# ProPrj_X-Link_OB-RA4M2_M_2024-12-16.net
KiCad netlist of a schematic drawn in EasyEDA Pro
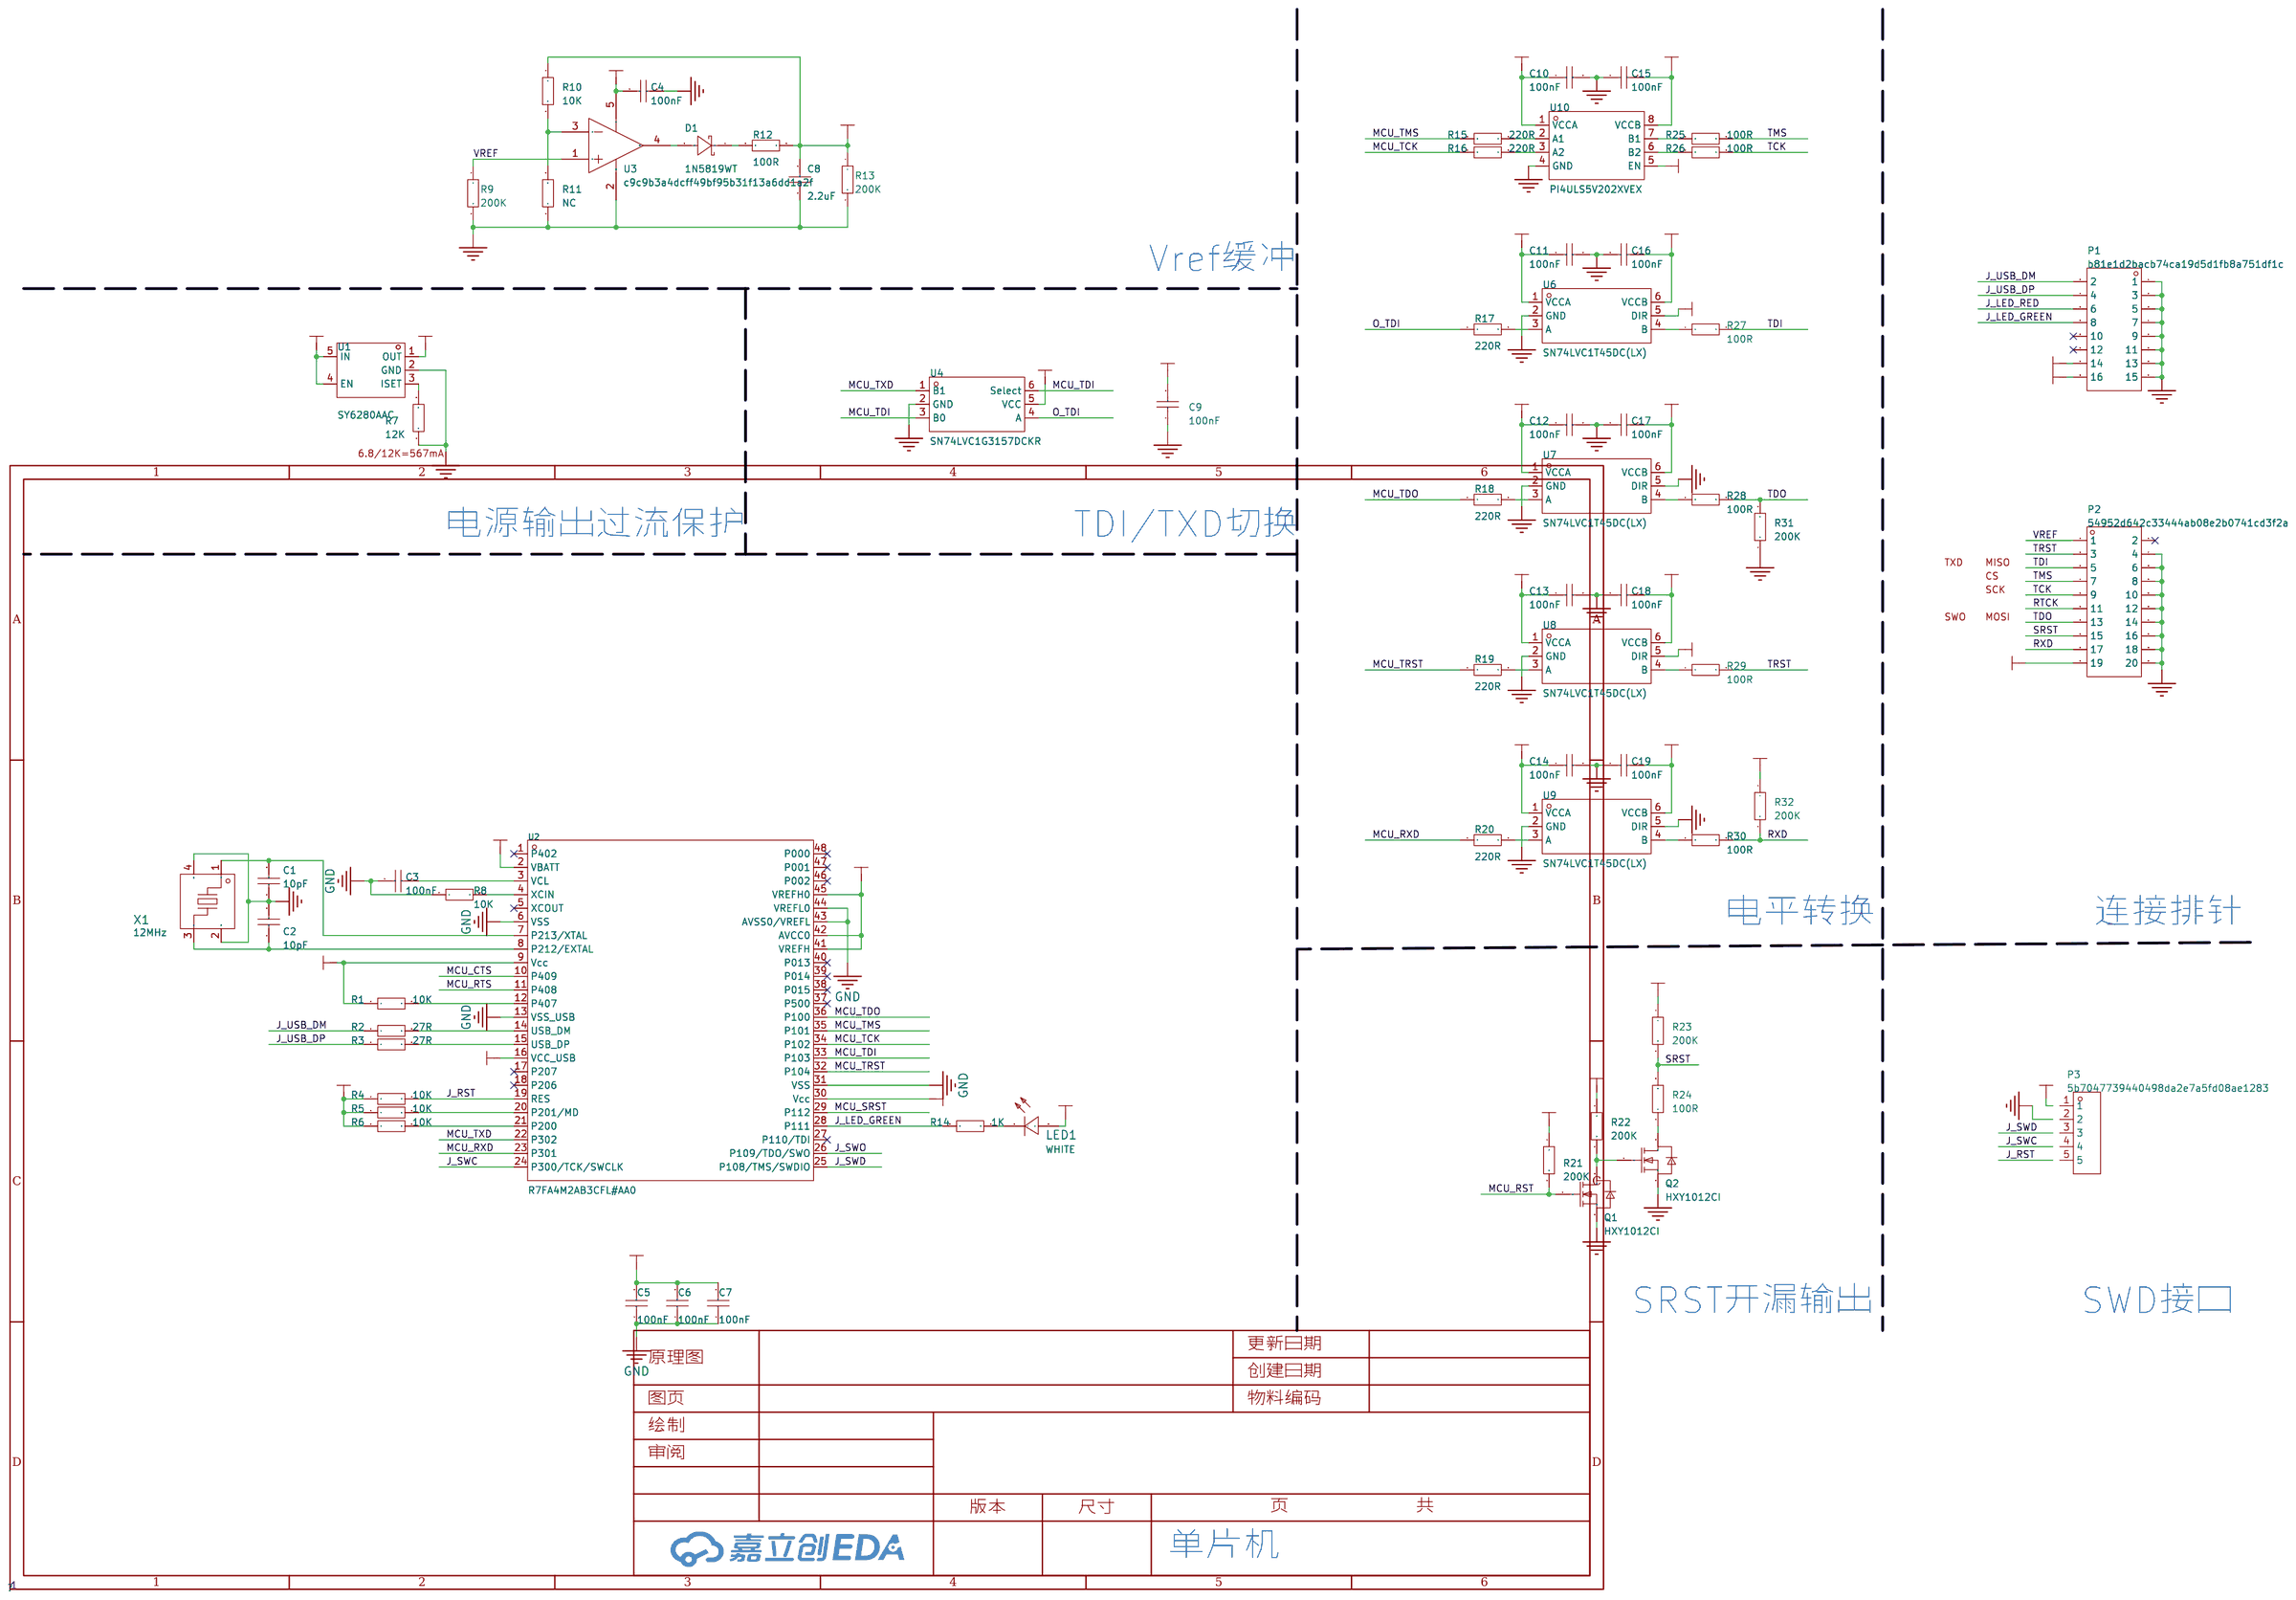
[diagram p0: schematic sheet]

(export (version "E")
  (design (tool "Eeschema 10.0.6"))
  (components
    (comp (ref "C1")
      (value "10pF")
      (footprint "easyedapro:C0805")
      (description "容值:20pF;精度:±5%;额定电压:50V;材质(温度系数):C0G;")
      (fields
        (field (name "Manufacturer Part") "CL21C200JBANNNC")
        (field (name "Manufacturer") "SAMSUNG(三星)")
      )
      (libsource (lib "easyedapro") (part "CL21C200JBANNNC"))
    )
    (comp (ref "C2")
      (value "10pF")
      (footprint "easyedapro:C0805")
      (description "容值:20pF;精度:±5%;额定电压:50V;材质(温度系数):C0G;")
      (fields
        (field (name "Manufacturer Part") "CL21C200JBANNNC")
        (field (name "Manufacturer") "SAMSUNG(三星)")
      )
      (libsource (lib "easyedapro") (part "CL21C200JBANNNC"))
    )
    (comp (ref "C3")
      (value "100nF")
      (footprint "easyedapro:C0805")
      (description "容值:100nF;精度:±10%;额定电压:50V;材质(温度系数):X7R;")
      (fields
        (field (name "Manufacturer Part") "CC0805KRX7R9BB104")
        (field (name "Manufacturer") "YAGEO(国巨)")
      )
      (libsource (lib "easyedapro") (part "CC0805KRX7R9BB104"))
    )
    (comp (ref "C4")
      (value "100nF")
      (footprint "easyedapro:C0402")
      (libsource (lib "easyedapro") (part "C0402"))
    )
    (comp (ref "C5")
      (value "100nF")
      (footprint "easyedapro:C0805")
      (description "容值:100nF;精度:±10%;额定电压:50V;材质(温度系数):X7R;")
      (fields
        (field (name "Manufacturer Part") "CC0805KRX7R9BB104")
        (field (name "Manufacturer") "YAGEO(国巨)")
      )
      (libsource (lib "easyedapro") (part "CC0805KRX7R9BB104"))
    )
    (comp (ref "C6")
      (value "100nF")
      (footprint "easyedapro:C0805")
      (description "容值:100nF;精度:±10%;额定电压:50V;材质(温度系数):X7R;")
      (fields
        (field (name "Manufacturer Part") "CC0805KRX7R9BB104")
        (field (name "Manufacturer") "YAGEO(国巨)")
      )
      (libsource (lib "easyedapro") (part "CC0805KRX7R9BB104"))
    )
    (comp (ref "C7")
      (value "100nF")
      (footprint "easyedapro:C0805")
      (description "容值:100nF;精度:±10%;额定电压:50V;材质(温度系数):X7R;")
      (fields
        (field (name "Manufacturer Part") "CC0805KRX7R9BB104")
        (field (name "Manufacturer") "YAGEO(国巨)")
      )
      (libsource (lib "easyedapro") (part "CC0805KRX7R9BB104"))
    )
    (comp (ref "C8")
      (value "2.2uF")
      (footprint "easyedapro:C0402")
      (libsource (lib "easyedapro") (part "C0402"))
    )
    (comp (ref "C9")
      (value "100nF")
      (footprint "easyedapro:C0603")
      (libsource (lib "easyedapro") (part "C0603"))
    )
    (comp (ref "C10")
      (value "100nF")
      (footprint "easyedapro:C0603")
      (libsource (lib "easyedapro") (part "C0603"))
    )
    (comp (ref "C11")
      (value "100nF")
      (footprint "easyedapro:C0603")
      (libsource (lib "easyedapro") (part "C0603"))
    )
    (comp (ref "C12")
      (value "100nF")
      (footprint "easyedapro:C0603")
      (libsource (lib "easyedapro") (part "C0603"))
    )
    (comp (ref "C13")
      (value "100nF")
      (footprint "easyedapro:C0603")
      (libsource (lib "easyedapro") (part "C0603"))
    )
    (comp (ref "C14")
      (value "100nF")
      (footprint "easyedapro:C0603")
      (libsource (lib "easyedapro") (part "C0603"))
    )
    (comp (ref "C15")
      (value "100nF")
      (footprint "easyedapro:C0603")
      (libsource (lib "easyedapro") (part "C0603"))
    )
    (comp (ref "C16")
      (value "100nF")
      (footprint "easyedapro:C0603")
      (libsource (lib "easyedapro") (part "C0603"))
    )
    (comp (ref "C17")
      (value "100nF")
      (footprint "easyedapro:C0603")
      (libsource (lib "easyedapro") (part "C0603"))
    )
    (comp (ref "C18")
      (value "100nF")
      (footprint "easyedapro:C0603")
      (libsource (lib "easyedapro") (part "C0603"))
    )
    (comp (ref "C19")
      (value "100nF")
      (footprint "easyedapro:C0603")
      (libsource (lib "easyedapro") (part "C0603"))
    )
    (comp (ref "D1")
      (value "1N5819WT")
      (footprint "easyedapro:SOD-523_L1.2-W0.8-LS1.6-RD")
      (description "二极管配置:独立式;正向压降(Vf):600mV@200mA;直流反向耐压(Vr):40V;整流电流:350mA;")
      (fields (field (name "Manufacturer") "Slkor(萨科微)"))
      (libsource (lib "easyedapro") (part "1N5819WT_C5185918"))
    )
    (comp (ref "LED1")
      (value "WHITE")
      (footprint "easyedapro:LED0603")
      (libsource (lib "easyedapro") (part "LED0603"))
    )
    (comp (ref "P1")
      (value "b81e1d2bacb74ca19d5d1fb8a751df1c")
      (footprint "easyedapro:HDR-TH_16P-P1.27-V-M-R2-C8-S1.27-1")
      (libsource (lib "easyedapro") (part "HDR2x8_1.27"))
    )
    (comp (ref "P2")
      (value "54952d642c33444ab08e2b0741cd3f2a")
      (footprint "easyedapro:HDR-TH_20P-P1.27-V-M-R2-C10-S1.27")
      (libsource (lib "easyedapro") (part "HDR2x10_1.27"))
    )
    (comp (ref "P3")
      (value "5b7047739440498da2e7a5fd08ae1283")
      (footprint "easyedapro:HDR-TH_5P-P1.27-V-M")
      (libsource (lib "easyedapro") (part "HDR1x5_1.27"))
    )
    (comp (ref "Q1")
      (value "HXY1012CI")
      (footprint "easyedapro:SOT-523-3_L1.6-W0.8-P0.50-LS1.6-BR")
      (fields (field (name "Manufacturer") "HXY MOSFET(华轩阳电子)"))
      (libsource (lib "easyedapro") (part "HXY1012CI"))
    )
    (comp (ref "Q2")
      (value "HXY1012CI")
      (footprint "easyedapro:SOT-523-3_L1.6-W0.8-P0.50-LS1.6-BR")
      (fields (field (name "Manufacturer") "HXY MOSFET(华轩阳电子)"))
      (libsource (lib "easyedapro") (part "HXY1012CI"))
    )
    (comp (ref "R1")
      (value "10K")
      (footprint "easyedapro:R0805")
      (description "阻值:10kΩ;精度:±1%;功率:125mW;温度系数:±100ppm/°C;最大工作电压:150V;工作温度范围:-55°C~+155°C;")
      (fields (field (name "Manufacturer Part") "RC0805FR-0710KL") (field (name "Manufacturer") "YAGEO(国巨)"))
      (libsource (lib "easyedapro") (part "RC0805FR-0710KL"))
    )
    (comp (ref "R2")
      (value "27R")
      (footprint "easyedapro:R0805")
      (description "电阻类型:厚膜电阻;阻值:27Ω;精度:±1%;功率:125mW;")
      (fields (field (name "Manufacturer Part") "RC0805FR-0727RL") (field (name "Manufacturer") "YAGEO(国巨)"))
      (libsource (lib "easyedapro") (part "RC0805FR-0727RL"))
    )
    (comp (ref "R3")
      (value "27R")
      (footprint "easyedapro:R0805")
      (description "电阻类型:厚膜电阻;阻值:27Ω;精度:±1%;功率:125mW;")
      (fields (field (name "Manufacturer Part") "RC0805FR-0727RL") (field (name "Manufacturer") "YAGEO(国巨)"))
      (libsource (lib "easyedapro") (part "RC0805FR-0727RL"))
    )
    (comp (ref "R4")
      (value "10K")
      (footprint "easyedapro:R0805")
      (description "阻值:10kΩ;精度:±1%;功率:125mW;温度系数:±100ppm/°C;最大工作电压:150V;工作温度范围:-55°C~+155°C;")
      (fields (field (name "Manufacturer Part") "RC0805FR-0710KL") (field (name "Manufacturer") "YAGEO(国巨)"))
      (libsource (lib "easyedapro") (part "RC0805FR-0710KL"))
    )
    (comp (ref "R5")
      (value "10K")
      (footprint "easyedapro:R0805")
      (description "阻值:10kΩ;精度:±1%;功率:125mW;温度系数:±100ppm/°C;最大工作电压:150V;工作温度范围:-55°C~+155°C;")
      (fields (field (name "Manufacturer Part") "RC0805FR-0710KL") (field (name "Manufacturer") "YAGEO(国巨)"))
      (libsource (lib "easyedapro") (part "RC0805FR-0710KL"))
    )
    (comp (ref "R6")
      (value "10K")
      (footprint "easyedapro:R0805")
      (description "阻值:10kΩ;精度:±1%;功率:125mW;温度系数:±100ppm/°C;最大工作电压:150V;工作温度范围:-55°C~+155°C;")
      (fields (field (name "Manufacturer Part") "RC0805FR-0710KL") (field (name "Manufacturer") "YAGEO(国巨)"))
      (libsource (lib "easyedapro") (part "RC0805FR-0710KL"))
    )
    (comp (ref "R7")
      (value "12K")
      (footprint "easyedapro:R0603")
      (libsource (lib "easyedapro") (part "R0603"))
    )
    (comp (ref "R8")
      (value "10K")
      (footprint "easyedapro:R0805")
      (description "阻值:10kΩ;精度:±1%;功率:125mW;温度系数:±100ppm/°C;最大工作电压:150V;工作温度范围:-55°C~+155°C;")
      (fields (field (name "Manufacturer Part") "RC0805FR-0710KL") (field (name "Manufacturer") "YAGEO(国巨)"))
      (libsource (lib "easyedapro") (part "RC0805FR-0710KL"))
    )
    (comp (ref "R9")
      (value "200K")
      (footprint "easyedapro:R0402")
      (libsource (lib "easyedapro") (part "R0402"))
    )
    (comp (ref "R10")
      (value "10K")
      (footprint "easyedapro:R0402")
      (libsource (lib "easyedapro") (part "R0402"))
    )
    (comp (ref "R11")
      (value "NC")
      (footprint "easyedapro:R0402")
      (libsource (lib "easyedapro") (part "R0402"))
    )
    (comp (ref "R12")
      (value "100R")
      (footprint "easyedapro:R0402")
      (libsource (lib "easyedapro") (part "R0402"))
    )
    (comp (ref "R13")
      (value "200K")
      (footprint "easyedapro:R0402")
      (libsource (lib "easyedapro") (part "R0402"))
    )
    (comp (ref "R14")
      (value "1K")
      (footprint "easyedapro:R0805")
      (description "电阻类型:厚膜电阻;阻值:5.1kΩ;精度:±1%;功率:125mW;")
      (fields
        (field (name "Manufacturer Part") "0805W8F5101T5E")
        (field (name "Manufacturer") "UNI-ROYAL(厚声)")
      )
      (libsource (lib "easyedapro") (part "0805W8F5101T5E"))
    )
    (comp (ref "R15") (value "220R") (libsource (lib "easyedapro") (part "电阻")))
    (comp (ref "R16") (value "220R") (libsource (lib "easyedapro") (part "电阻")))
    (comp (ref "R17")
      (value "220R")
      (footprint "easyedapro:R0603")
      (libsource (lib "easyedapro") (part "R0603"))
    )
    (comp (ref "R18")
      (value "220R")
      (footprint "easyedapro:R0603")
      (libsource (lib "easyedapro") (part "R0603"))
    )
    (comp (ref "R19")
      (value "220R")
      (footprint "easyedapro:R0603")
      (libsource (lib "easyedapro") (part "R0603"))
    )
    (comp (ref "R20")
      (value "220R")
      (footprint "easyedapro:R0603")
      (libsource (lib "easyedapro") (part "R0603"))
    )
    (comp (ref "R21") (value "200K") (libsource (lib "easyedapro") (part "电阻")))
    (comp (ref "R22") (value "200K") (libsource (lib "easyedapro") (part "电阻")))
    (comp (ref "R23") (value "200K") (libsource (lib "easyedapro") (part "电阻")))
    (comp (ref "R24") (value "100R") (libsource (lib "easyedapro") (part "电阻")))
    (comp (ref "R25") (value "100R") (libsource (lib "easyedapro") (part "电阻")))
    (comp (ref "R26") (value "100R") (libsource (lib "easyedapro") (part "电阻")))
    (comp (ref "R27")
      (value "100R")
      (footprint "easyedapro:R0603")
      (libsource (lib "easyedapro") (part "R0603"))
    )
    (comp (ref "R28")
      (value "100R")
      (footprint "easyedapro:R0603")
      (libsource (lib "easyedapro") (part "R0603"))
    )
    (comp (ref "R29")
      (value "100R")
      (footprint "easyedapro:R0603")
      (libsource (lib "easyedapro") (part "R0603"))
    )
    (comp (ref "R30")
      (value "100R")
      (footprint "easyedapro:R0603")
      (libsource (lib "easyedapro") (part "R0603"))
    )
    (comp (ref "R31")
      (value "200K")
      (footprint "easyedapro:R0603")
      (libsource (lib "easyedapro") (part "R0603"))
    )
    (comp (ref "R32")
      (value "200K")
      (footprint "easyedapro:R0603")
      (libsource (lib "easyedapro") (part "R0603"))
    )
    (comp (ref "U1")
      (value "SY6280AAC")
      (footprint "easyedapro:SOT-23-5_L3.0-W1.7-P0.95-LS2.8-BL")
      (description "低能耗配电开关")
      (fields (field (name "Manufacturer") "silergy(矽力杰)"))
      (libsource (lib "easyedapro") (part "SY6280AAC"))
    )
    (comp (ref "U2")
      (value "R7FA4M2AB3CFL#AA0")
      (footprint "easyedapro:LQFP-48_L7.0-W7.0-P0.50-LS9.0-BL")
      (description "CPU内核:ARM-M系列;CPU最大主频:100MHz;工作电压范围:2.7V~3.6V;程序存储容量:254KB;GPIO端口数量:30;")
      (fields (field (name "Manufacturer") "RENESAS(瑞萨)/IDT"))
      (libsource (lib "easyedapro") (part "R7FA4M2AB3CFL#AA0"))
    )
    (comp (ref "U3")
      (value "c9c9b3a4dcff49bf95b31f13a6dd1a2f")
      (footprint "easyedapro:SOT-23-5_L2.9-W1.6-P0.95-LS2.8-BR")
      (description "轨到轨输入输出单运放")
      (fields (field (name "Manufacturer Part") "LMV321"))
      (libsource (lib "easyedapro") (part "LMV321"))
    )
    (comp (ref "U4")
      (value "SN74LVC1G3157DCKR")
      (footprint "easyedapro:SC70-6_L2.1-W1.3-P0.65-LS2.3-BL")
      (description "开关电路:单刀双掷(SPDT)-常开/常闭;通道数:1;导通电阻(Ron@VCC):7Ω;")
      (fields (field (name "Manufacturer") "UMW(友台半导体)"))
      (libsource (lib "easyedapro") (part "SN74LVC1G3157DCKR-1"))
    )
    (comp (ref "U6")
      (value "SN74LVC1T45DC(LX)")
      (footprint "easyedapro:SC-70-6_L2.2-W1.3-P0.65-LS2.1-BR")
      (description "电压(VCCA):1.65V~5.5V;电压(VCCB):1.65V~5.5V;电路数:1;每个电路通道数:1;")
      (fields (field (name "Manufacturer") "LX(灵星芯微)"))
      (libsource (lib "easyedapro") (part "74LVC1T45DW-7"))
    )
    (comp (ref "U7")
      (value "SN74LVC1T45DC(LX)")
      (footprint "easyedapro:SC-70-6_L2.2-W1.3-P0.65-LS2.1-BR")
      (description "电压(VCCA):1.65V~5.5V;电压(VCCB):1.65V~5.5V;电路数:1;每个电路通道数:1;")
      (fields (field (name "Manufacturer") "LX(灵星芯微)"))
      (libsource (lib "easyedapro") (part "74LVC1T45DW-7"))
    )
    (comp (ref "U8")
      (value "SN74LVC1T45DC(LX)")
      (footprint "easyedapro:SC-70-6_L2.2-W1.3-P0.65-LS2.1-BR")
      (description "电压(VCCA):1.65V~5.5V;电压(VCCB):1.65V~5.5V;电路数:1;每个电路通道数:1;")
      (fields (field (name "Manufacturer") "LX(灵星芯微)"))
      (libsource (lib "easyedapro") (part "74LVC1T45DW-7"))
    )
    (comp (ref "U9")
      (value "SN74LVC1T45DC(LX)")
      (footprint "easyedapro:SC-70-6_L2.2-W1.3-P0.65-LS2.1-BR")
      (description "电压(VCCA):1.65V~5.5V;电压(VCCB):1.65V~5.5V;电路数:1;每个电路通道数:1;")
      (fields (field (name "Manufacturer") "LX(灵星芯微)"))
      (libsource (lib "easyedapro") (part "74LVC1T45DW-7"))
    )
    (comp (ref "U10")
      (value "PI4ULS5V202XVEX")
      (footprint "easyedapro:UDFN-8_L1.6-W1.2-P0.40-BL")
      (description "数据速率:20Mbps;电压(VCCA):1.2V~5.5V;电压(VCCB):1.2V~5.5V;电路数:1;每个电路通道数:2;")
      (fields (field (name "Manufacturer") "DIODES(美台)"))
      (libsource (lib "easyedapro") (part "PI4ULS5V202XVEX"))
    )
    (comp (ref "X1")
      (value "12MHz")
      (footprint "easyedapro:CRYSTAL-SMD_4P-L3.2-W2.5-BL-A")
      (libsource (lib "easyedapro") (part "XTAL3225"))
    )
  )
  (nets
    (net (code "1") (name "/J_LED_GREEN") (class "Default")
      (node (ref "P1") (pin "8") (pinfunction "8_8") (pintype "unspecified"))
      (node (ref "R14") (pin "1") (pinfunction "1_1") (pintype "input"))
      (node (ref "U2") (pin "28") (pinfunction "P111_28") (pintype "input"))
    )
    (net (code "2") (name "/J_LED_RED") (class "Default")
      (node (ref "P1") (pin "6") (pinfunction "6_6") (pintype "unspecified"))
    )
    (net (code "3") (name "/J_RST") (class "Default")
      (node (ref "R4") (pin "2") (pinfunction "2_2") (pintype "input"))
      (node (ref "U2") (pin "19") (pinfunction "RES_19") (pintype "input"))
    )
    (net (code "4") (name "/J_SWC") (class "Default")
      (node (ref "U2") (pin "24") (pinfunction "P300/TCK/SWCLK_24") (pintype "input"))
    )
    (net (code "5") (name "/J_SWD") (class "Default")
      (node (ref "U2") (pin "25") (pinfunction "P108/TMS/SWDIO_25") (pintype "input"))
    )
    (net (code "6") (name "/J_SWO") (class "Default")
      (node (ref "U2") (pin "26") (pinfunction "P109/TDO/SWO_26") (pintype "input"))
    )
    (net (code "7") (name "/J_USB_DM") (class "Default")
      (node (ref "P1") (pin "2") (pinfunction "2_2") (pintype "unspecified"))
      (node (ref "R2") (pin "1") (pinfunction "1_1") (pintype "input"))
    )
    (net (code "8") (name "/J_USB_DP") (class "Default")
      (node (ref "P1") (pin "4") (pinfunction "4_4") (pintype "unspecified"))
      (node (ref "R3") (pin "1") (pinfunction "1_1") (pintype "input"))
    )
    (net (code "9") (name "/MCU_CTS") (class "Default")
      (node (ref "U2") (pin "10") (pinfunction "P409_10") (pintype "input"))
    )
    (net (code "10") (name "/MCU_RST") (class "Default")
      (node (ref "Q1") (pin "1") (pinfunction "G_1") (pintype "unspecified"))
      (node (ref "R21") (pin "2") (pinfunction "2_2") (pintype "input"))
    )
    (net (code "11") (name "/MCU_RTS") (class "Default")
      (node (ref "U2") (pin "11") (pinfunction "P408_11") (pintype "input"))
    )
    (net (code "12") (name "/MCU_RXD") (class "Default")
      (node (ref "R20") (pin "1") (pinfunction "1_1") (pintype "input"))
      (node (ref "U2") (pin "23") (pinfunction "P301_23") (pintype "input"))
    )
    (net (code "13") (name "/MCU_SRST") (class "Default")
      (node (ref "U2") (pin "29") (pinfunction "P112_29") (pintype "input"))
    )
    (net (code "14") (name "/MCU_TCK") (class "Default")
      (node (ref "R16") (pin "1") (pinfunction "1_1") (pintype "input"))
      (node (ref "U2") (pin "34") (pinfunction "P102_34") (pintype "input"))
    )
    (net (code "15") (name "/MCU_TDI") (class "Default")
      (node (ref "U2") (pin "33") (pinfunction "P103_33") (pintype "input"))
      (node (ref "U4") (pin "3") (pinfunction "B0_3") (pintype "unspecified"))
      (node (ref "U4") (pin "6") (pinfunction "Select_6") (pintype "unspecified"))
    )
    (net (code "16") (name "/MCU_TDO") (class "Default")
      (node (ref "R18") (pin "1") (pinfunction "1_1") (pintype "input"))
      (node (ref "U2") (pin "36") (pinfunction "P100_36") (pintype "input"))
    )
    (net (code "17") (name "/MCU_TMS") (class "Default")
      (node (ref "R15") (pin "1") (pinfunction "1_1") (pintype "input"))
      (node (ref "U2") (pin "35") (pinfunction "P101_35") (pintype "input"))
    )
    (net (code "18") (name "/MCU_TRST") (class "Default")
      (node (ref "R19") (pin "1") (pinfunction "1_1") (pintype "input"))
      (node (ref "U2") (pin "32") (pinfunction "P104_32") (pintype "input"))
    )
    (net (code "19") (name "/MCU_TXD") (class "Default")
      (node (ref "U2") (pin "22") (pinfunction "P302_22") (pintype "input"))
      (node (ref "U4") (pin "1") (pinfunction "B1_1") (pintype "unspecified"))
    )
    (net (code "20") (name "/O_TDI") (class "Default")
      (node (ref "R17") (pin "1") (pinfunction "1_1") (pintype "input"))
      (node (ref "U4") (pin "4") (pinfunction "A_4") (pintype "unspecified"))
    )
    (net (code "21") (name "/RTCK") (class "Default")
      (node (ref "P2") (pin "11") (pinfunction "11_11") (pintype "unspecified"))
    )
    (net (code "22") (name "/RXD") (class "Default")
      (node (ref "P2") (pin "17") (pinfunction "17_17") (pintype "unspecified"))
      (node (ref "R30") (pin "2") (pinfunction "2_2") (pintype "input"))
      (node (ref "R32") (pin "2") (pinfunction "2_2") (pintype "input"))
    )
    (net (code "23") (name "/SRST") (class "Default")
      (node (ref "P2") (pin "15") (pinfunction "15_15") (pintype "unspecified"))
      (node (ref "R23") (pin "2") (pinfunction "2_2") (pintype "input"))
      (node (ref "R24") (pin "2") (pinfunction "2_2") (pintype "input"))
    )
    (net (code "24") (name "/TCK") (class "Default")
      (node (ref "P2") (pin "9") (pinfunction "9_9") (pintype "unspecified"))
      (node (ref "R26") (pin "2") (pinfunction "2_2") (pintype "input"))
    )
    (net (code "25") (name "/TDI") (class "Default")
      (node (ref "P2") (pin "5") (pinfunction "5_5") (pintype "unspecified"))
      (node (ref "R27") (pin "2") (pinfunction "2_2") (pintype "input"))
    )
    (net (code "26") (name "/TDO") (class "Default")
      (node (ref "P2") (pin "13") (pinfunction "13_13") (pintype "unspecified"))
      (node (ref "R28") (pin "2") (pinfunction "2_2") (pintype "input"))
      (node (ref "R31") (pin "2") (pinfunction "2_2") (pintype "input"))
    )
    (net (code "27") (name "/TMS") (class "Default")
      (node (ref "P2") (pin "7") (pinfunction "7_7") (pintype "unspecified"))
      (node (ref "R25") (pin "2") (pinfunction "2_2") (pintype "input"))
    )
    (net (code "28") (name "/TRST") (class "Default")
      (node (ref "P2") (pin "3") (pinfunction "3_3") (pintype "unspecified"))
      (node (ref "R29") (pin "2") (pinfunction "2_2") (pintype "input"))
    )
    (net (code "29") (name "/VREF") (class "Default")
      (node (ref "P2") (pin "1") (pinfunction "1_1") (pintype "unspecified"))
      (node (ref "R9") (pin "1") (pinfunction "1_1") (pintype "input"))
      (node (ref "U3") (pin "1") (pinfunction "+IN_1") (pintype "unspecified"))
    )
    (net (code "30") (name "3.3V") (class "Default")
      (node (ref "C10") (pin "1") (pinfunction "1_1") (pintype "input"))
      (node (ref "C11") (pin "1") (pinfunction "1_1") (pintype "input"))
      (node (ref "C12") (pin "1") (pinfunction "1_1") (pintype "input"))
      (node (ref "C13") (pin "1") (pinfunction "1_1") (pintype "input"))
      (node (ref "C14") (pin "1") (pinfunction "1_1") (pintype "input"))
      (node (ref "C5") (pin "2") (pinfunction "2_2") (pintype "input"))
      (node (ref "C6") (pin "2") (pinfunction "2_2") (pintype "input"))
      (node (ref "C7") (pin "2") (pinfunction "2_2") (pintype "input"))
      (node (ref "C9") (pin "2") (pinfunction "2_2") (pintype "input"))
      (node (ref "LED1") (pin "2") (pinfunction "+_2") (pintype "input"))
      (node (ref "P1") (pin "14") (pinfunction "14_14") (pintype "unspecified"))
      (node (ref "R1") (pin "1") (pinfunction "1_1") (pintype "input"))
      (node (ref "R21") (pin "1") (pinfunction "1_1") (pintype "input"))
      (node (ref "R22") (pin "1") (pinfunction "1_1") (pintype "input"))
      (node (ref "R4") (pin "1") (pinfunction "1_1") (pintype "input"))
      (node (ref "R5") (pin "1") (pinfunction "1_1") (pintype "input"))
      (node (ref "R6") (pin "1") (pinfunction "1_1") (pintype "input"))
      (node (ref "U10") (pin "1") (pinfunction "VCCA_1") (pintype "unspecified"))
      (node (ref "U10") (pin "5") (pinfunction "EN_5") (pintype "unspecified"))
      (node (ref "U2") (pin "16") (pinfunction "VCC_USB_16") (pintype "input"))
      (node (ref "U2") (pin "2") (pinfunction "VBATT_2") (pintype "input"))
      (node (ref "U2") (pin "30") (pinfunction "Vcc_30") (pintype "input"))
      (node (ref "U2") (pin "41") (pinfunction "VREFH_41") (pintype "input"))
      (node (ref "U2") (pin "42") (pinfunction "AVCC0_42") (pintype "input"))
      (node (ref "U2") (pin "45") (pinfunction "VREFH0_45") (pintype "input"))
      (node (ref "U2") (pin "9") (pinfunction "Vcc_9") (pintype "input"))
      (node (ref "U4") (pin "5") (pinfunction "VCC_5") (pintype "unspecified"))
      (node (ref "U6") (pin "1") (pinfunction "VCCA_1") (pintype "unspecified"))
      (node (ref "U6") (pin "5") (pinfunction "DIR_5") (pintype "unspecified"))
      (node (ref "U7") (pin "1") (pinfunction "VCCA_1") (pintype "unspecified"))
      (node (ref "U8") (pin "1") (pinfunction "VCCA_1") (pintype "unspecified"))
      (node (ref "U8") (pin "5") (pinfunction "DIR_5") (pintype "unspecified"))
      (node (ref "U9") (pin "1") (pinfunction "VCCA_1") (pintype "unspecified"))
    )
    (net (code "31") (name "5V") (class "Default")
      (node (ref "C4") (pin "1") (pinfunction "1_1") (pintype "input"))
      (node (ref "P1") (pin "16") (pinfunction "16_16") (pintype "unspecified"))
      (node (ref "U1") (pin "4") (pinfunction "EN_4") (pintype "unspecified"))
      (node (ref "U1") (pin "5") (pinfunction "IN_5") (pintype "unspecified"))
      (node (ref "U3") (pin "5") (pinfunction "VCC+_5") (pintype "unspecified"))
    )
    (net (code "32") (name "5V_OUT") (class "Default")
      (node (ref "P2") (pin "19") (pinfunction "19_19") (pintype "unspecified"))
      (node (ref "U1") (pin "1") (pinfunction "OUT_1") (pintype "unspecified"))
    )
    (net (code "33") (name "GND") (class "Default")
      (node (ref "C1") (pin "1") (pinfunction "1_1") (pintype "input"))
      (node (ref "C10") (pin "2") (pinfunction "2_2") (pintype "input"))
      (node (ref "C11") (pin "2") (pinfunction "2_2") (pintype "input"))
      (node (ref "C12") (pin "2") (pinfunction "2_2") (pintype "input"))
      (node (ref "C13") (pin "2") (pinfunction "2_2") (pintype "input"))
      (node (ref "C14") (pin "2") (pinfunction "2_2") (pintype "input"))
      (node (ref "C15") (pin "1") (pinfunction "1_1") (pintype "input"))
      (node (ref "C16") (pin "1") (pinfunction "1_1") (pintype "input"))
      (node (ref "C17") (pin "1") (pinfunction "1_1") (pintype "input"))
      (node (ref "C18") (pin "1") (pinfunction "1_1") (pintype "input"))
      (node (ref "C19") (pin "1") (pinfunction "1_1") (pintype "input"))
      (node (ref "C2") (pin "2") (pinfunction "2_2") (pintype "input"))
      (node (ref "C3") (pin "1") (pinfunction "1_1") (pintype "input"))
      (node (ref "C4") (pin "2") (pinfunction "2_2") (pintype "input"))
      (node (ref "C5") (pin "1") (pinfunction "1_1") (pintype "input"))
      (node (ref "C6") (pin "1") (pinfunction "1_1") (pintype "input"))
      (node (ref "C7") (pin "1") (pinfunction "1_1") (pintype "input"))
      (node (ref "C8") (pin "1") (pinfunction "1_1") (pintype "input"))
      (node (ref "C9") (pin "1") (pinfunction "1_1") (pintype "input"))
      (node (ref "P1") (pin "1") (pinfunction "1_1") (pintype "unspecified"))
      (node (ref "P1") (pin "11") (pinfunction "11_11") (pintype "unspecified"))
      (node (ref "P1") (pin "13") (pinfunction "13_13") (pintype "unspecified"))
      (node (ref "P1") (pin "15") (pinfunction "15_15") (pintype "unspecified"))
      (node (ref "P1") (pin "3") (pinfunction "3_3") (pintype "unspecified"))
      (node (ref "P1") (pin "5") (pinfunction "5_5") (pintype "unspecified"))
      (node (ref "P1") (pin "7") (pinfunction "7_7") (pintype "unspecified"))
      (node (ref "P1") (pin "9") (pinfunction "9_9") (pintype "unspecified"))
      (node (ref "P2") (pin "10") (pinfunction "10_10") (pintype "unspecified"))
      (node (ref "P2") (pin "12") (pinfunction "12_12") (pintype "unspecified"))
      (node (ref "P2") (pin "14") (pinfunction "14_14") (pintype "unspecified"))
      (node (ref "P2") (pin "16") (pinfunction "16_16") (pintype "unspecified"))
      (node (ref "P2") (pin "18") (pinfunction "18_18") (pintype "unspecified"))
      (node (ref "P2") (pin "20") (pinfunction "20_20") (pintype "unspecified"))
      (node (ref "P2") (pin "4") (pinfunction "4_4") (pintype "unspecified"))
      (node (ref "P2") (pin "6") (pinfunction "6_6") (pintype "unspecified"))
      (node (ref "P2") (pin "8") (pinfunction "8_8") (pintype "unspecified"))
      (node (ref "Q1") (pin "2") (pinfunction "S_2") (pintype "unspecified"))
      (node (ref "Q2") (pin "2") (pinfunction "S_2") (pintype "unspecified"))
      (node (ref "R11") (pin "1") (pinfunction "1_1") (pintype "input"))
      (node (ref "R13") (pin "2") (pinfunction "2_2") (pintype "input"))
      (node (ref "R31") (pin "1") (pinfunction "1_1") (pintype "input"))
      (node (ref "R7") (pin "1") (pinfunction "1_1") (pintype "input"))
      (node (ref "R8") (pin "1") (pinfunction "1_1") (pintype "input"))
      (node (ref "R9") (pin "2") (pinfunction "2_2") (pintype "input"))
      (node (ref "U1") (pin "2") (pinfunction "GND_2") (pintype "unspecified"))
      (node (ref "U10") (pin "4") (pinfunction "GND_4") (pintype "unspecified"))
      (node (ref "U2") (pin "13") (pinfunction "VSS_USB_13") (pintype "input"))
      (node (ref "U2") (pin "31") (pinfunction "VSS_31") (pintype "input"))
      (node (ref "U2") (pin "43") (pinfunction "AVSS0/VREFL_43") (pintype "input"))
      (node (ref "U2") (pin "44") (pinfunction "VREFL0_44") (pintype "input"))
      (node (ref "U2") (pin "6") (pinfunction "VSS_6") (pintype "input"))
      (node (ref "U3") (pin "2") (pinfunction "GND_2") (pintype "unspecified"))
      (node (ref "U4") (pin "2") (pinfunction "GND_2") (pintype "unspecified"))
      (node (ref "U6") (pin "2") (pinfunction "GND_2") (pintype "unspecified"))
      (node (ref "U7") (pin "2") (pinfunction "GND_2") (pintype "unspecified"))
      (node (ref "U7") (pin "5") (pinfunction "DIR_5") (pintype "unspecified"))
      (node (ref "U8") (pin "2") (pinfunction "GND_2") (pintype "unspecified"))
      (node (ref "U9") (pin "2") (pinfunction "GND_2") (pintype "unspecified"))
      (node (ref "U9") (pin "5") (pinfunction "DIR_5") (pintype "unspecified"))
      (node (ref "X1") (pin "2") (pinfunction "GND_2") (pintype "input"))
      (node (ref "X1") (pin "4") (pinfunction "GND_4") (pintype "input"))
    )
    (net (code "34") (name "Net-(D1-Pad1)") (class "Default")
      (node (ref "D1") (pin "1") (pinfunction "1_1") (pintype "unspecified"))
      (node (ref "R12") (pin "2") (pinfunction "2_2") (pintype "input"))
    )
    (net (code "35") (name "Net-(LED1--)") (class "Default")
      (node (ref "LED1") (pin "1") (pinfunction "-_1") (pintype "input"))
      (node (ref "R14") (pin "2") (pinfunction "2_2") (pintype "input"))
    )
    (net (code "36") (name "Net-(Q1-D)") (class "Default")
      (node (ref "Q1") (pin "3") (pinfunction "D_3") (pintype "unspecified"))
      (node (ref "Q2") (pin "1") (pinfunction "G_1") (pintype "unspecified"))
      (node (ref "R22") (pin "2") (pinfunction "2_2") (pintype "input"))
    )
    (net (code "37") (name "Net-(Q2-D)") (class "Default")
      (node (ref "Q2") (pin "3") (pinfunction "D_3") (pintype "unspecified"))
      (node (ref "R24") (pin "1") (pinfunction "1_1") (pintype "input"))
    )
    (net (code "38") (name "Net-(U1-ISET)") (class "Default")
      (node (ref "R7") (pin "2") (pinfunction "2_2") (pintype "input"))
      (node (ref "U1") (pin "3") (pinfunction "ISET_3") (pintype "unspecified"))
    )
    (net (code "39") (name "Net-(U2-P200)") (class "Default")
      (node (ref "R6") (pin "2") (pinfunction "2_2") (pintype "input"))
      (node (ref "U2") (pin "21") (pinfunction "P200_21") (pintype "input"))
    )
    (net (code "40") (name "Net-(U2-P201{slash}MD)") (class "Default")
      (node (ref "R5") (pin "2") (pinfunction "2_2") (pintype "input"))
      (node (ref "U2") (pin "20") (pinfunction "P201/MD_20") (pintype "input"))
    )
    (net (code "41") (name "Net-(U2-P212{slash}EXTAL)") (class "Default")
      (node (ref "C2") (pin "1") (pinfunction "1_1") (pintype "input"))
      (node (ref "U2") (pin "8") (pinfunction "P212/EXTAL_8") (pintype "input"))
      (node (ref "X1") (pin "3") (pinfunction "3_3") (pintype "input"))
    )
    (net (code "42") (name "Net-(U2-P213{slash}XTAL)") (class "Default")
      (node (ref "C1") (pin "2") (pinfunction "2_2") (pintype "input"))
      (node (ref "U2") (pin "7") (pinfunction "P213/XTAL_7") (pintype "input"))
      (node (ref "X1") (pin "1") (pinfunction "1_1") (pintype "input"))
    )
    (net (code "43") (name "Net-(U2-P407)") (class "Default")
      (node (ref "R1") (pin "2") (pinfunction "2_2") (pintype "input"))
      (node (ref "U2") (pin "12") (pinfunction "P407_12") (pintype "input"))
    )
    (net (code "44") (name "Net-(U2-USB_DM)") (class "Default")
      (node (ref "R2") (pin "2") (pinfunction "2_2") (pintype "input"))
      (node (ref "U2") (pin "14") (pinfunction "USB_DM_14") (pintype "input"))
    )
    (net (code "45") (name "Net-(U2-USB_DP)") (class "Default")
      (node (ref "R3") (pin "2") (pinfunction "2_2") (pintype "input"))
      (node (ref "U2") (pin "15") (pinfunction "USB_DP_15") (pintype "input"))
    )
    (net (code "46") (name "Net-(U2-VCL)") (class "Default")
      (node (ref "C3") (pin "2") (pinfunction "2_2") (pintype "input"))
      (node (ref "U2") (pin "3") (pinfunction "VCL_3") (pintype "input"))
    )
    (net (code "47") (name "Net-(U2-XCIN)") (class "Default")
      (node (ref "R8") (pin "2") (pinfunction "2_2") (pintype "input"))
      (node (ref "U2") (pin "4") (pinfunction "XCIN_4") (pintype "input"))
    )
    (net (code "48") (name "Net-(U3--IN)") (class "Default")
      (node (ref "R10") (pin "2") (pinfunction "2_2") (pintype "input"))
      (node (ref "R11") (pin "2") (pinfunction "2_2") (pintype "input"))
      (node (ref "U3") (pin "3") (pinfunction "-IN_3") (pintype "unspecified"))
    )
    (net (code "49") (name "Net-(U3-OUT)") (class "Default")
      (node (ref "D1") (pin "2") (pinfunction "2_2") (pintype "unspecified"))
      (node (ref "U3") (pin "4") (pinfunction "OUT_4") (pintype "output"))
    )
    (net (code "50") (name "Net-(U6-A)") (class "Default")
      (node (ref "R17") (pin "2") (pinfunction "2_2") (pintype "input"))
      (node (ref "U6") (pin "3") (pinfunction "A_3") (pintype "unspecified"))
    )
    (net (code "51") (name "Net-(U6-B)") (class "Default")
      (node (ref "R27") (pin "1") (pinfunction "1_1") (pintype "input"))
      (node (ref "U6") (pin "4") (pinfunction "B_4") (pintype "unspecified"))
    )
    (net (code "52") (name "Net-(U7-A)") (class "Default")
      (node (ref "R18") (pin "2") (pinfunction "2_2") (pintype "input"))
      (node (ref "U7") (pin "3") (pinfunction "A_3") (pintype "unspecified"))
    )
    (net (code "53") (name "Net-(U7-B)") (class "Default")
      (node (ref "R28") (pin "1") (pinfunction "1_1") (pintype "input"))
      (node (ref "U7") (pin "4") (pinfunction "B_4") (pintype "unspecified"))
    )
    (net (code "54") (name "Net-(U8-A)") (class "Default")
      (node (ref "R19") (pin "2") (pinfunction "2_2") (pintype "input"))
      (node (ref "U8") (pin "3") (pinfunction "A_3") (pintype "unspecified"))
    )
    (net (code "55") (name "Net-(U8-B)") (class "Default")
      (node (ref "R29") (pin "1") (pinfunction "1_1") (pintype "input"))
      (node (ref "U8") (pin "4") (pinfunction "B_4") (pintype "unspecified"))
    )
    (net (code "56") (name "Net-(U9-A)") (class "Default")
      (node (ref "R20") (pin "2") (pinfunction "2_2") (pintype "input"))
      (node (ref "U9") (pin "3") (pinfunction "A_3") (pintype "unspecified"))
    )
    (net (code "57") (name "Net-(U9-B)") (class "Default")
      (node (ref "R30") (pin "1") (pinfunction "1_1") (pintype "input"))
      (node (ref "U9") (pin "4") (pinfunction "B_4") (pintype "unspecified"))
    )
    (net (code "58") (name "Net-(U10-A1)") (class "Default")
      (node (ref "R15") (pin "2") (pinfunction "2_2") (pintype "input"))
      (node (ref "U10") (pin "2") (pinfunction "A1_2") (pintype "unspecified"))
    )
    (net (code "59") (name "Net-(U10-A2)") (class "Default")
      (node (ref "R16") (pin "2") (pinfunction "2_2") (pintype "input"))
      (node (ref "U10") (pin "3") (pinfunction "A2_3") (pintype "unspecified"))
    )
    (net (code "60") (name "Net-(U10-B1)") (class "Default")
      (node (ref "R25") (pin "1") (pinfunction "1_1") (pintype "input"))
      (node (ref "U10") (pin "7") (pinfunction "B1_7") (pintype "unspecified"))
    )
    (net (code "61") (name "Net-(U10-B2)") (class "Default")
      (node (ref "R26") (pin "1") (pinfunction "1_1") (pintype "input"))
      (node (ref "U10") (pin "6") (pinfunction "B2_6") (pintype "unspecified"))
    )
    (net (code "62") (name "VIO") (class "Default")
      (node (ref "C15") (pin "2") (pinfunction "2_2") (pintype "input"))
      (node (ref "C16") (pin "2") (pinfunction "2_2") (pintype "input"))
      (node (ref "C17") (pin "2") (pinfunction "2_2") (pintype "input"))
      (node (ref "C18") (pin "2") (pinfunction "2_2") (pintype "input"))
      (node (ref "C19") (pin "2") (pinfunction "2_2") (pintype "input"))
      (node (ref "C8") (pin "2") (pinfunction "2_2") (pintype "input"))
      (node (ref "R10") (pin "1") (pinfunction "1_1") (pintype "input"))
      (node (ref "R12") (pin "1") (pinfunction "1_1") (pintype "input"))
      (node (ref "R13") (pin "1") (pinfunction "1_1") (pintype "input"))
      (node (ref "R23") (pin "1") (pinfunction "1_1") (pintype "input"))
      (node (ref "R32") (pin "1") (pinfunction "1_1") (pintype "input"))
      (node (ref "U10") (pin "8") (pinfunction "VCCB_8") (pintype "unspecified"))
      (node (ref "U6") (pin "6") (pinfunction "VCCB_6") (pintype "unspecified"))
      (node (ref "U7") (pin "6") (pinfunction "VCCB_6") (pintype "unspecified"))
      (node (ref "U8") (pin "6") (pinfunction "VCCB_6") (pintype "unspecified"))
      (node (ref "U9") (pin "6") (pinfunction "VCCB_6") (pintype "unspecified"))
    )
    (net (code "63") (name "unconnected-(P1-Pad10)") (class "Default")
      (node (ref "P1") (pin "10") (pinfunction "10_10") (pintype "unspecified+no_connect"))
    )
    (net (code "64") (name "unconnected-(P1-Pad12)") (class "Default")
      (node (ref "P1") (pin "12") (pinfunction "12_12") (pintype "unspecified+no_connect"))
    )
    (net (code "65") (name "unconnected-(P2-Pad2)") (class "Default")
      (node (ref "P2") (pin "2") (pinfunction "2_2") (pintype "unspecified+no_connect"))
    )
    (net (code "66") (name "unconnected-(P3-Pad1)") (class "Default")
      (node (ref "P3") (pin "1") (pinfunction "1_1") (pintype "unspecified"))
    )
    (net (code "67") (name "unconnected-(P3-Pad2)") (class "Default")
      (node (ref "P3") (pin "2") (pinfunction "2_2") (pintype "unspecified"))
    )
    (net (code "68") (name "unconnected-(P3-Pad3)") (class "Default")
      (node (ref "P3") (pin "3") (pinfunction "3_3") (pintype "unspecified"))
    )
    (net (code "69") (name "unconnected-(P3-Pad4)") (class "Default")
      (node (ref "P3") (pin "4") (pinfunction "4_4") (pintype "unspecified"))
    )
    (net (code "70") (name "unconnected-(P3-Pad5)") (class "Default")
      (node (ref "P3") (pin "5") (pinfunction "5_5") (pintype "unspecified"))
    )
    (net (code "71") (name "unconnected-(U2-P000-Pad48)") (class "Default")
      (node (ref "U2") (pin "48") (pinfunction "P000_48") (pintype "input+no_connect"))
    )
    (net (code "72") (name "unconnected-(U2-P001-Pad47)") (class "Default")
      (node (ref "U2") (pin "47") (pinfunction "P001_47") (pintype "input+no_connect"))
    )
    (net (code "73") (name "unconnected-(U2-P002-Pad46)") (class "Default")
      (node (ref "U2") (pin "46") (pinfunction "P002_46") (pintype "input+no_connect"))
    )
    (net (code "74") (name "unconnected-(U2-P013-Pad40)") (class "Default")
      (node (ref "U2") (pin "40") (pinfunction "P013_40") (pintype "input+no_connect"))
    )
    (net (code "75") (name "unconnected-(U2-P014-Pad39)") (class "Default")
      (node (ref "U2") (pin "39") (pinfunction "P014_39") (pintype "input+no_connect"))
    )
    (net (code "76") (name "unconnected-(U2-P015-Pad38)") (class "Default")
      (node (ref "U2") (pin "38") (pinfunction "P015_38") (pintype "input+no_connect"))
    )
    (net (code "77") (name "unconnected-(U2-P110{slash}TDI-Pad27)") (class "Default")
      (node (ref "U2") (pin "27") (pinfunction "P110/TDI_27") (pintype "input+no_connect"))
    )
    (net (code "78") (name "unconnected-(U2-P206-Pad18)") (class "Default")
      (node (ref "U2") (pin "18") (pinfunction "P206_18") (pintype "input+no_connect"))
    )
    (net (code "79") (name "unconnected-(U2-P207-Pad17)") (class "Default")
      (node (ref "U2") (pin "17") (pinfunction "P207_17") (pintype "input+no_connect"))
    )
    (net (code "80") (name "unconnected-(U2-P402-Pad1)") (class "Default")
      (node (ref "U2") (pin "1") (pinfunction "P402_1") (pintype "input+no_connect"))
    )
    (net (code "81") (name "unconnected-(U2-P500-Pad37)") (class "Default")
      (node (ref "U2") (pin "37") (pinfunction "P500_37") (pintype "input+no_connect"))
    )
    (net (code "82") (name "unconnected-(U2-XCOUT-Pad5)") (class "Default")
      (node (ref "U2") (pin "5") (pinfunction "XCOUT_5") (pintype "input+no_connect"))
    )
  )
)
